# ai_ft232_breakout.net
KiCad netlist of a schematic drawn in EAGLE
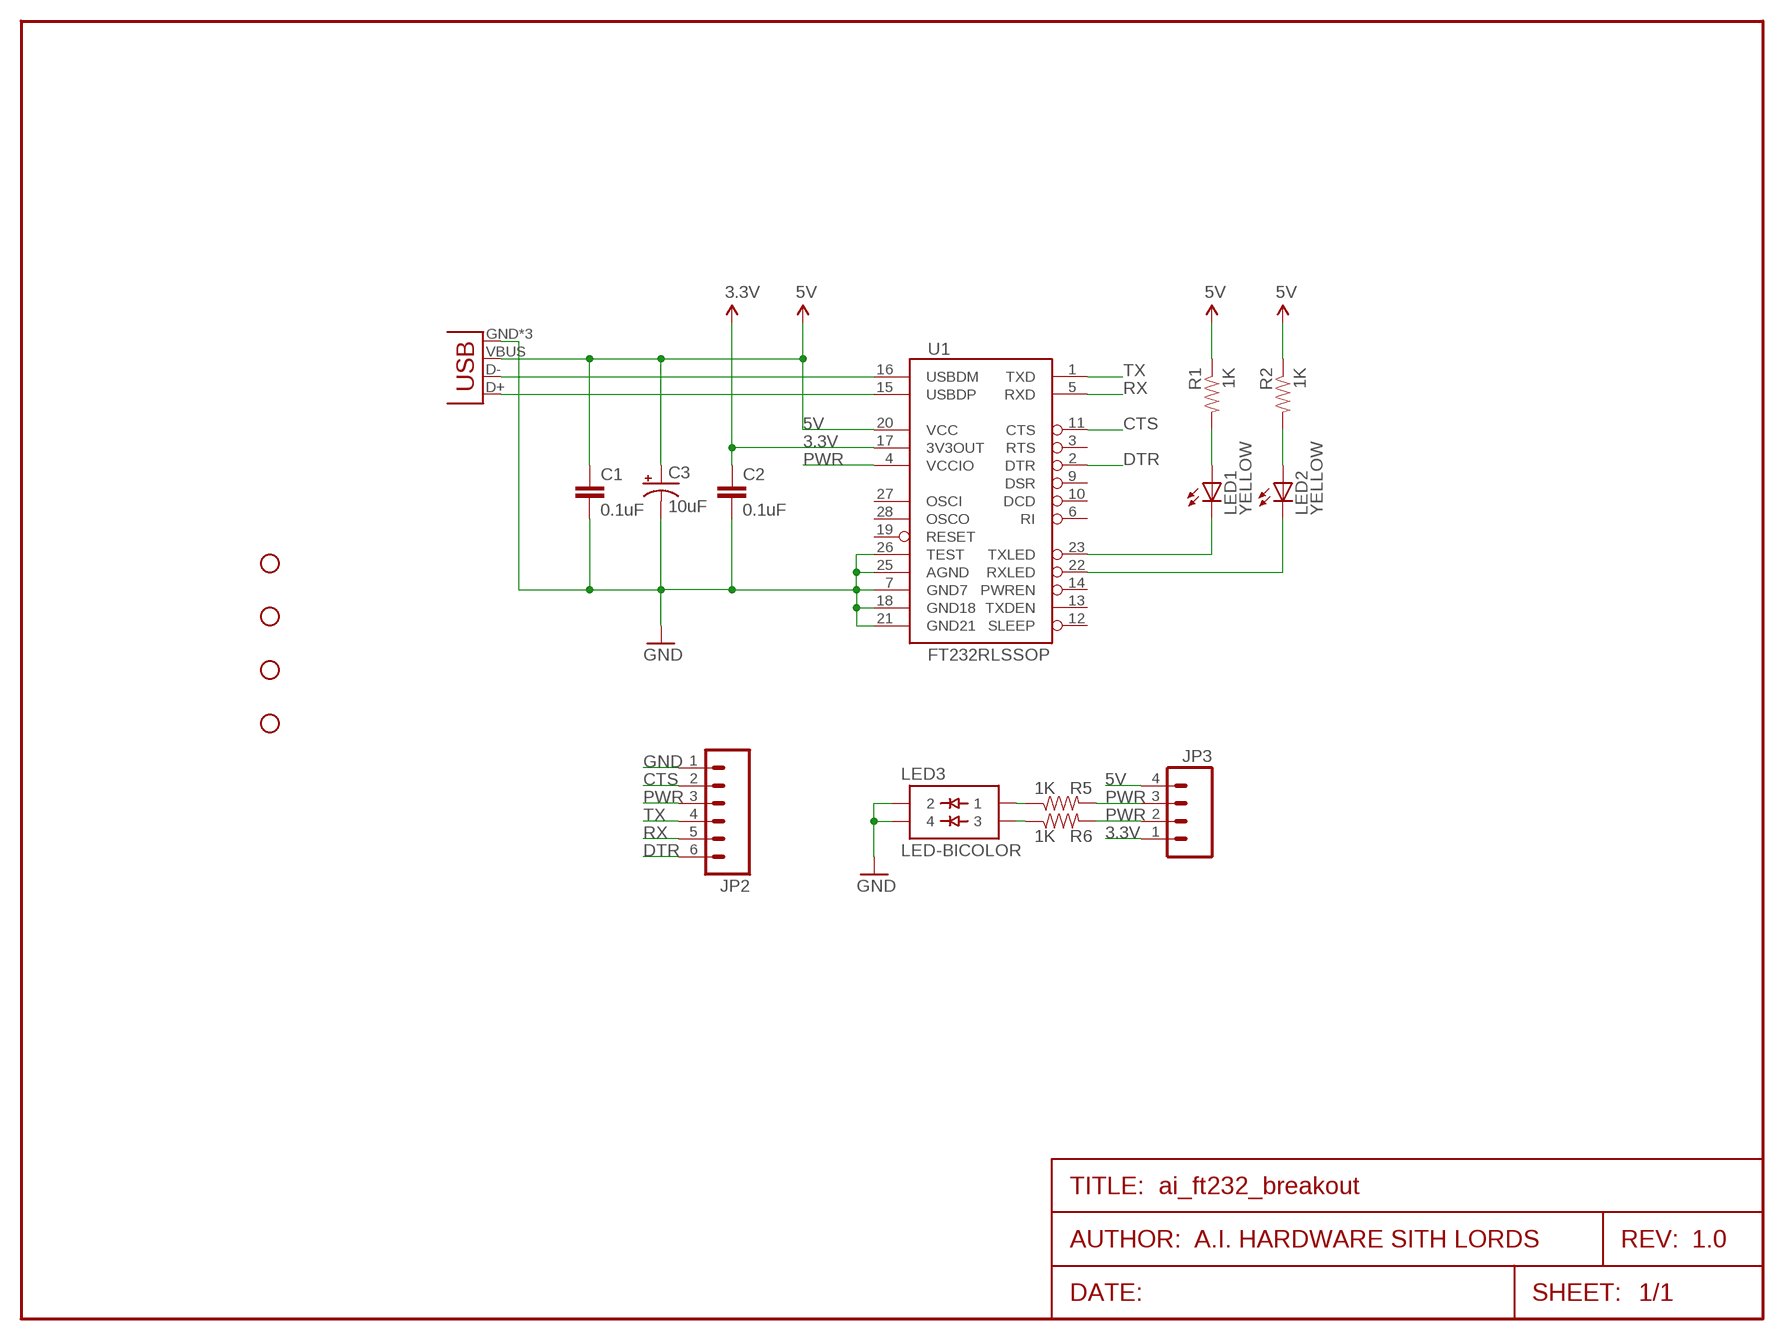
[diagram p0: schematic, sheet 1]

(export (version "E")
  (design (tool "Eeschema 10.0.6"))
  (components
    (comp (ref "C1")
      (value "0.1uF")
      (footprint "eagle-import:0805")
      (libsource (lib "eagle-import") (part "CAP0805"))
    )
    (comp (ref "C2")
      (value "0.1uF")
      (footprint "eagle-import:0805")
      (libsource (lib "eagle-import") (part "CAP0805"))
    )
    (comp (ref "C3")
      (value "10uF")
      (footprint "eagle-import:EIA3216-KIT")
      (libsource (lib "eagle-import") (part "CAP_POL1206-KIT"))
    )
    (comp (ref "JP2")
      (value "M06LONGPADS")
      (footprint "eagle-import:1X06_LONGPADS")
      (libsource (lib "eagle-import") (part "M06LONGPADS"))
    )
    (comp (ref "JP3")
      (value "M04PTH")
      (footprint "eagle-import:1X04")
      (libsource (lib "eagle-import") (part "M04PTH"))
    )
    (comp (ref "LED1")
      (value "YELLOW")
      (footprint "eagle-import:LED-0603")
      (libsource (lib "eagle-import") (part "LED-RED0603"))
    )
    (comp (ref "LED2")
      (value "YELLOW")
      (footprint "eagle-import:LED-0603")
      (libsource (lib "eagle-import") (part "LED-GREEN0603"))
    )
    (comp (ref "LED3")
      (value "LED-BICOLOR")
      (footprint "eagle-import:LED-BICOLOR-SMD")
      (libsource (lib "eagle-import") (part "LED-BICOLOR"))
    )
    (comp (ref "R1")
      (value "1K")
      (footprint "eagle-import:0805")
      (libsource (lib "eagle-import") (part "RESISTOR0805-RES"))
    )
    (comp (ref "R2")
      (value "1K")
      (footprint "eagle-import:0805")
      (libsource (lib "eagle-import") (part "RESISTOR0805-RES"))
    )
    (comp (ref "R5")
      (value "1K")
      (footprint "eagle-import:0805")
      (libsource (lib "eagle-import") (part "RESISTOR0805-RES"))
    )
    (comp (ref "R6")
      (value "1K")
      (footprint "eagle-import:0805")
      (libsource (lib "eagle-import") (part "RESISTOR0805-RES"))
    )
    (comp (ref "STANDOFF1")
      (value "STAND-OFF")
      (footprint "eagle-import:STAND-OFF")
      (libsource (lib "eagle-import") (part "STAND-OFF"))
    )
    (comp (ref "STANDOFF2")
      (value "STAND-OFF")
      (footprint "eagle-import:STAND-OFF")
      (libsource (lib "eagle-import") (part "STAND-OFF"))
    )
    (comp (ref "STANDOFF3")
      (value "STAND-OFF")
      (footprint "eagle-import:STAND-OFF")
      (libsource (lib "eagle-import") (part "STAND-OFF"))
    )
    (comp (ref "STANDOFF4")
      (value "STAND-OFF")
      (footprint "eagle-import:STAND-OFF")
      (libsource (lib "eagle-import") (part "STAND-OFF"))
    )
    (comp (ref "U1")
      (value "FT232RLSSOP")
      (footprint "eagle-import:SSOP28DB")
      (libsource (lib "eagle-import") (part "FT232RLSSOP"))
    )
    (comp (ref "USB")
      (value "USB-MICROB")
      (footprint "eagle-import:USB-MICROB")
      (libsource (lib "eagle-import") (part "USB-MICROB"))
    )
  )
  (nets
    (net (code "1") (name "/CTS") (class "Default")
      (node (ref "JP2") (pin "2") (pinfunction "2_2") (pintype "passive"))
      (node (ref "U1") (pin "11") (pinfunction "CTS_11") (pintype "input"))
    )
    (net (code "2") (name "/DTR") (class "Default")
      (node (ref "JP2") (pin "6") (pinfunction "6_6") (pintype "passive"))
      (node (ref "U1") (pin "2") (pinfunction "DTR_2") (pintype "output"))
    )
    (net (code "3") (name "/PWR") (class "Default")
      (node (ref "JP2") (pin "3") (pinfunction "3_3") (pintype "passive"))
      (node (ref "JP3") (pin "2") (pinfunction "2_2") (pintype "passive"))
      (node (ref "R6") (pin "2") (pinfunction "2_2") (pintype "passive"))
      (node (ref "U1") (pin "4") (pinfunction "VCCIO_4") (pintype "power_in"))
    )
    (net (code "4") (name "/RX") (class "Default")
      (node (ref "JP2") (pin "5") (pinfunction "5_5") (pintype "passive"))
      (node (ref "U1") (pin "5") (pinfunction "RXD_5") (pintype "input"))
    )
    (net (code "5") (name "/TX") (class "Default")
      (node (ref "JP2") (pin "4") (pinfunction "4_4") (pintype "passive"))
      (node (ref "U1") (pin "1") (pinfunction "TXD_1") (pintype "output"))
    )
    (net (code "6") (name "3.3V") (class "Default")
      (node (ref "C2") (pin "1") (pinfunction "1_1") (pintype "passive"))
      (node (ref "JP3") (pin "1") (pinfunction "1_1") (pintype "passive"))
      (node (ref "U1") (pin "17") (pinfunction "3V3OUT_17") (pintype "output"))
    )
    (net (code "7") (name "5V") (class "Default")
      (node (ref "C1") (pin "1") (pinfunction "1_1") (pintype "passive"))
      (node (ref "C3") (pin "A") (pinfunction "+_A") (pintype "passive"))
      (node (ref "JP3") (pin "4") (pinfunction "4_4") (pintype "passive"))
      (node (ref "R1") (pin "1") (pinfunction "1_1") (pintype "passive"))
      (node (ref "R2") (pin "1") (pinfunction "1_1") (pintype "passive"))
      (node (ref "U1") (pin "20") (pinfunction "VCC_20") (pintype "power_in"))
      (node (ref "USB") (pin "VBUS") (pinfunction "VBUS_VBUS") (pintype "bidirectional"))
    )
    (net (code "8") (name "GND") (class "Default")
      (node (ref "C1") (pin "2") (pinfunction "2_2") (pintype "passive"))
      (node (ref "C2") (pin "2") (pinfunction "2_2") (pintype "passive"))
      (node (ref "C3") (pin "C") (pinfunction "-_C") (pintype "passive"))
      (node (ref "JP2") (pin "1") (pinfunction "1_1") (pintype "passive"))
      (node (ref "LED3") (pin "2") (pinfunction "4_2") (pintype "bidirectional"))
      (node (ref "LED3") (pin "3") (pinfunction "2_3") (pintype "bidirectional"))
      (node (ref "U1") (pin "18") (pinfunction "GND18_18") (pintype "power_in"))
      (node (ref "U1") (pin "21") (pinfunction "GND21_21") (pintype "power_in"))
      (node (ref "U1") (pin "25") (pinfunction "AGND_25") (pintype "power_in"))
      (node (ref "U1") (pin "26") (pinfunction "TEST_26") (pintype "input"))
      (node (ref "U1") (pin "7") (pinfunction "GND7_7") (pintype "power_in"))
      (node (ref "USB") (pin "GND") (pinfunction "GND_GND") (pintype "bidirectional"))
      (node (ref "USB") (pin "MT1") (pinfunction "GND_MT1") (pintype "bidirectional"))
      (node (ref "USB") (pin "MT2") (pinfunction "GND_MT2") (pintype "bidirectional"))
    )
    (net (code "9") (name "Net-(JP3-Pad3)") (class "Default")
      (node (ref "JP3") (pin "3") (pinfunction "3_3") (pintype "passive"))
      (node (ref "R5") (pin "2") (pinfunction "2_2") (pintype "passive"))
    )
    (net (code "10") (name "Net-(LED1-PadA)") (class "Default")
      (node (ref "LED1") (pin "A") (pinfunction "A_A") (pintype "passive"))
      (node (ref "R1") (pin "2") (pinfunction "2_2") (pintype "passive"))
    )
    (net (code "11") (name "Net-(LED2-PadA)") (class "Default")
      (node (ref "LED2") (pin "A") (pinfunction "A_A") (pintype "passive"))
      (node (ref "R2") (pin "2") (pinfunction "2_2") (pintype "passive"))
    )
    (net (code "12") (name "Net-(LED3-3)") (class "Default")
      (node (ref "LED3") (pin "4") (pinfunction "3_4") (pintype "bidirectional"))
      (node (ref "R6") (pin "1") (pinfunction "1_1") (pintype "passive"))
    )
    (net (code "13") (name "Net-(LED3-Pad1)") (class "Default")
      (node (ref "LED3") (pin "1") (pinfunction "1_1") (pintype "bidirectional"))
      (node (ref "R5") (pin "1") (pinfunction "1_1") (pintype "passive"))
    )
    (net (code "14") (name "Net-(U1-RXLED)") (class "Default")
      (node (ref "LED2") (pin "C") (pinfunction "C_C") (pintype "passive"))
      (node (ref "U1") (pin "22") (pinfunction "RXLED_22") (pintype "input"))
    )
    (net (code "15") (name "Net-(U1-TXLED)") (class "Default")
      (node (ref "LED1") (pin "C") (pinfunction "C_C") (pintype "passive"))
      (node (ref "U1") (pin "23") (pinfunction "TXLED_23") (pintype "input"))
    )
    (net (code "16") (name "Net-(U1-USBDM)") (class "Default")
      (node (ref "U1") (pin "16") (pinfunction "USBDM_16") (pintype "bidirectional"))
      (node (ref "USB") (pin "D-") (pinfunction "D-_D-") (pintype "bidirectional"))
    )
    (net (code "17") (name "Net-(U1-USBDP)") (class "Default")
      (node (ref "U1") (pin "15") (pinfunction "USBDP_15") (pintype "bidirectional"))
      (node (ref "USB") (pin "D+") (pinfunction "D+_D+") (pintype "bidirectional"))
    )
    (net (code "18") (name "unconnected-(U1-DCD-Pad10)") (class "Default")
      (node (ref "U1") (pin "10") (pinfunction "DCD_10") (pintype "input"))
    )
    (net (code "19") (name "unconnected-(U1-DSR-Pad9)") (class "Default")
      (node (ref "U1") (pin "9") (pinfunction "DSR_9") (pintype "input"))
    )
    (net (code "20") (name "unconnected-(U1-OSCI-Pad27)") (class "Default")
      (node (ref "U1") (pin "27") (pinfunction "OSCI_27") (pintype "input"))
    )
    (net (code "21") (name "unconnected-(U1-OSCO-Pad28)") (class "Default")
      (node (ref "U1") (pin "28") (pinfunction "OSCO_28") (pintype "output"))
    )
    (net (code "22") (name "unconnected-(U1-PWREN-Pad14)") (class "Default")
      (node (ref "U1") (pin "14") (pinfunction "PWREN_14") (pintype "input"))
    )
    (net (code "23") (name "unconnected-(U1-RESET-Pad19)") (class "Default")
      (node (ref "U1") (pin "19") (pinfunction "RESET_19") (pintype "input"))
    )
    (net (code "24") (name "unconnected-(U1-RI-Pad6)") (class "Default")
      (node (ref "U1") (pin "6") (pinfunction "RI_6") (pintype "input"))
    )
    (net (code "25") (name "unconnected-(U1-RTS-Pad3)") (class "Default")
      (node (ref "U1") (pin "3") (pinfunction "RTS_3") (pintype "output"))
    )
    (net (code "26") (name "unconnected-(U1-SLEEP-Pad12)") (class "Default")
      (node (ref "U1") (pin "12") (pinfunction "SLEEP_12") (pintype "input"))
    )
    (net (code "27") (name "unconnected-(U1-TXDEN-Pad13)") (class "Default")
      (node (ref "U1") (pin "13") (pinfunction "TXDEN_13") (pintype "input"))
    )
  )
)
